# led_daughter.net
KiCad netlist of a schematic drawn in EAGLE
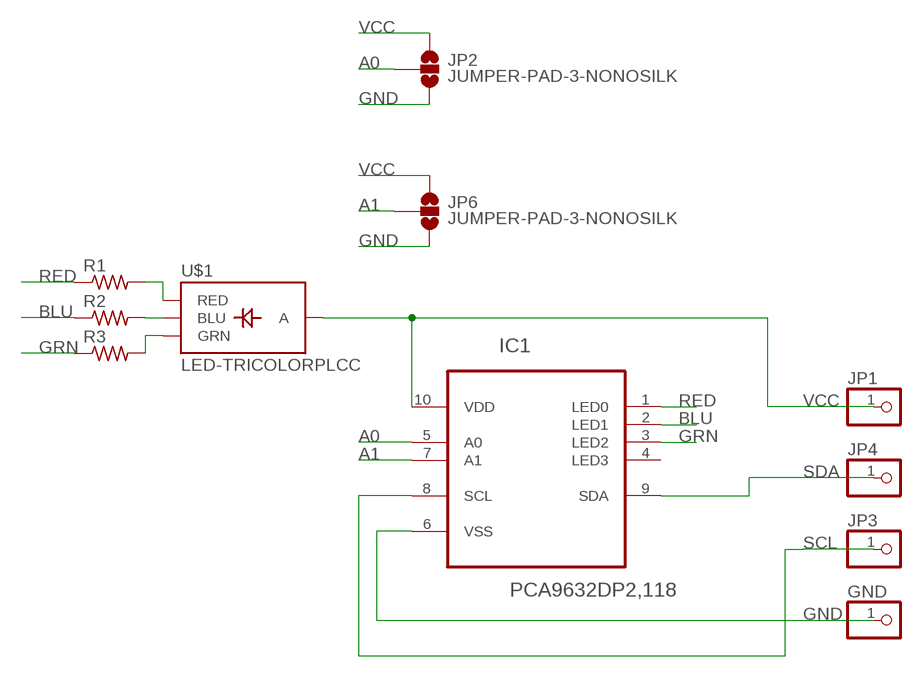
[diagram p0: schematic, sheet 1]

(export (version "E")
  (design (tool "Eeschema 10.0.6"))
  (components
    (comp (ref "GND")
      (value "PINHD-1X1CB")
      (footprint "eagle-import:1X01-CLEANBIG")
      (libsource (lib "eagle-import") (part "PINHD-1X1CB"))
    )
    (comp (ref "IC1")
      (value "PCA9632DP2,118")
      (footprint "eagle-import:SOP50P490X110-10N")
      (libsource (lib "eagle-import") (part "PCA9632DP2,118"))
    )
    (comp (ref "JP1")
      (value "PINHD-1X1CB")
      (footprint "eagle-import:1X01-CLEANBIG")
      (libsource (lib "eagle-import") (part "PINHD-1X1CB"))
    )
    (comp (ref "JP2")
      (value "JUMPER-PAD-3-NONOSILK")
      (footprint "eagle-import:PAD-JUMPER-3-NO_NO_SILK")
      (libsource (lib "eagle-import") (part "JUMPER-PAD-3-NONOSILK"))
    )
    (comp (ref "JP3")
      (value "PINHD-1X1CB")
      (footprint "eagle-import:1X01-CLEANBIG")
      (libsource (lib "eagle-import") (part "PINHD-1X1CB"))
    )
    (comp (ref "JP4")
      (value "PINHD-1X1CB")
      (footprint "eagle-import:1X01-CLEANBIG")
      (libsource (lib "eagle-import") (part "PINHD-1X1CB"))
    )
    (comp (ref "JP6")
      (value "JUMPER-PAD-3-NONOSILK")
      (footprint "eagle-import:PAD-JUMPER-3-NO_NO_SILK")
      (libsource (lib "eagle-import") (part "JUMPER-PAD-3-NONOSILK"))
    )
    (comp (ref "R1")
      (value "R-US_R0603")
      (footprint "eagle-import:R0603")
      (libsource (lib "eagle-import") (part "R-US_R0603"))
    )
    (comp (ref "R2")
      (value "R-US_R0603")
      (footprint "eagle-import:R0603")
      (libsource (lib "eagle-import") (part "R-US_R0603"))
    )
    (comp (ref "R3")
      (value "R-US_R0603")
      (footprint "eagle-import:R0603")
      (libsource (lib "eagle-import") (part "R-US_R0603"))
    )
    (comp (ref "U$1")
      (value "LED-TRICOLORPLCC")
      (footprint "eagle-import:LED-TRICOLOR-PLCC")
      (libsource (lib "eagle-import") (part "LED-TRICOLORPLCC"))
    )
  )
  (nets
    (net (code "1") (name "/A0") (class "Default")
      (node (ref "IC1") (pin "5") (pinfunction "A0_5") (pintype "input"))
      (node (ref "JP2") (pin "2") (pinfunction "2_2") (pintype "passive"))
    )
    (net (code "2") (name "/A1") (class "Default")
      (node (ref "IC1") (pin "7") (pinfunction "A1_7") (pintype "input"))
      (node (ref "JP6") (pin "2") (pinfunction "2_2") (pintype "passive"))
    )
    (net (code "3") (name "/BLU") (class "Default")
      (node (ref "IC1") (pin "2") (pinfunction "LED1_2") (pintype "output"))
      (node (ref "R2") (pin "1") (pinfunction "1_1") (pintype "passive"))
    )
    (net (code "4") (name "/GND") (class "Default")
      (node (ref "GND") (pin "1") (pinfunction "1_1") (pintype "passive"))
      (node (ref "IC1") (pin "6") (pinfunction "VSS_6") (pintype "power_in"))
      (node (ref "JP2") (pin "3") (pinfunction "3_3") (pintype "passive"))
      (node (ref "JP6") (pin "3") (pinfunction "3_3") (pintype "passive"))
    )
    (net (code "5") (name "/GRN") (class "Default")
      (node (ref "IC1") (pin "3") (pinfunction "LED2_3") (pintype "output"))
      (node (ref "R3") (pin "1") (pinfunction "1_1") (pintype "passive"))
    )
    (net (code "6") (name "/RED") (class "Default")
      (node (ref "IC1") (pin "1") (pinfunction "LED0_1") (pintype "output"))
      (node (ref "R1") (pin "1") (pinfunction "1_1") (pintype "passive"))
    )
    (net (code "7") (name "/SCL") (class "Default")
      (node (ref "IC1") (pin "8") (pinfunction "SCL_8") (pintype "input"))
      (node (ref "JP3") (pin "1") (pinfunction "1_1") (pintype "passive"))
    )
    (net (code "8") (name "/SDA") (class "Default")
      (node (ref "IC1") (pin "9") (pinfunction "SDA_9") (pintype "bidirectional"))
      (node (ref "JP4") (pin "1") (pinfunction "1_1") (pintype "passive"))
    )
    (net (code "9") (name "/VCC") (class "Default")
      (node (ref "IC1") (pin "10") (pinfunction "VDD_10") (pintype "power_in"))
      (node (ref "JP1") (pin "1") (pinfunction "1_1") (pintype "passive"))
      (node (ref "JP2") (pin "1") (pinfunction "1_1") (pintype "passive"))
      (node (ref "JP6") (pin "1") (pinfunction "1_1") (pintype "passive"))
      (node (ref "U$1") (pin "PAD1") (pinfunction "A_PAD1") (pintype "bidirectional"))
    )
    (net (code "10") (name "Net-(U$1-BLU)") (class "Default")
      (node (ref "R2") (pin "2") (pinfunction "2_2") (pintype "passive"))
      (node (ref "U$1") (pin "PAD2") (pinfunction "BLU_PAD2") (pintype "bidirectional"))
    )
    (net (code "11") (name "Net-(U$1-GRN)") (class "Default")
      (node (ref "R3") (pin "2") (pinfunction "2_2") (pintype "passive"))
      (node (ref "U$1") (pin "PAD3") (pinfunction "GRN_PAD3") (pintype "bidirectional"))
    )
    (net (code "12") (name "Net-(U$1-RED)") (class "Default")
      (node (ref "R1") (pin "2") (pinfunction "2_2") (pintype "passive"))
      (node (ref "U$1") (pin "PAD4") (pinfunction "RED_PAD4") (pintype "bidirectional"))
    )
    (net (code "13") (name "unconnected-(IC1-LED3-Pad4)") (class "Default")
      (node (ref "IC1") (pin "4") (pinfunction "LED3_4") (pintype "output"))
    )
  )
)
